# working.net
KiCad netlist of a schematic drawn in EAGLE
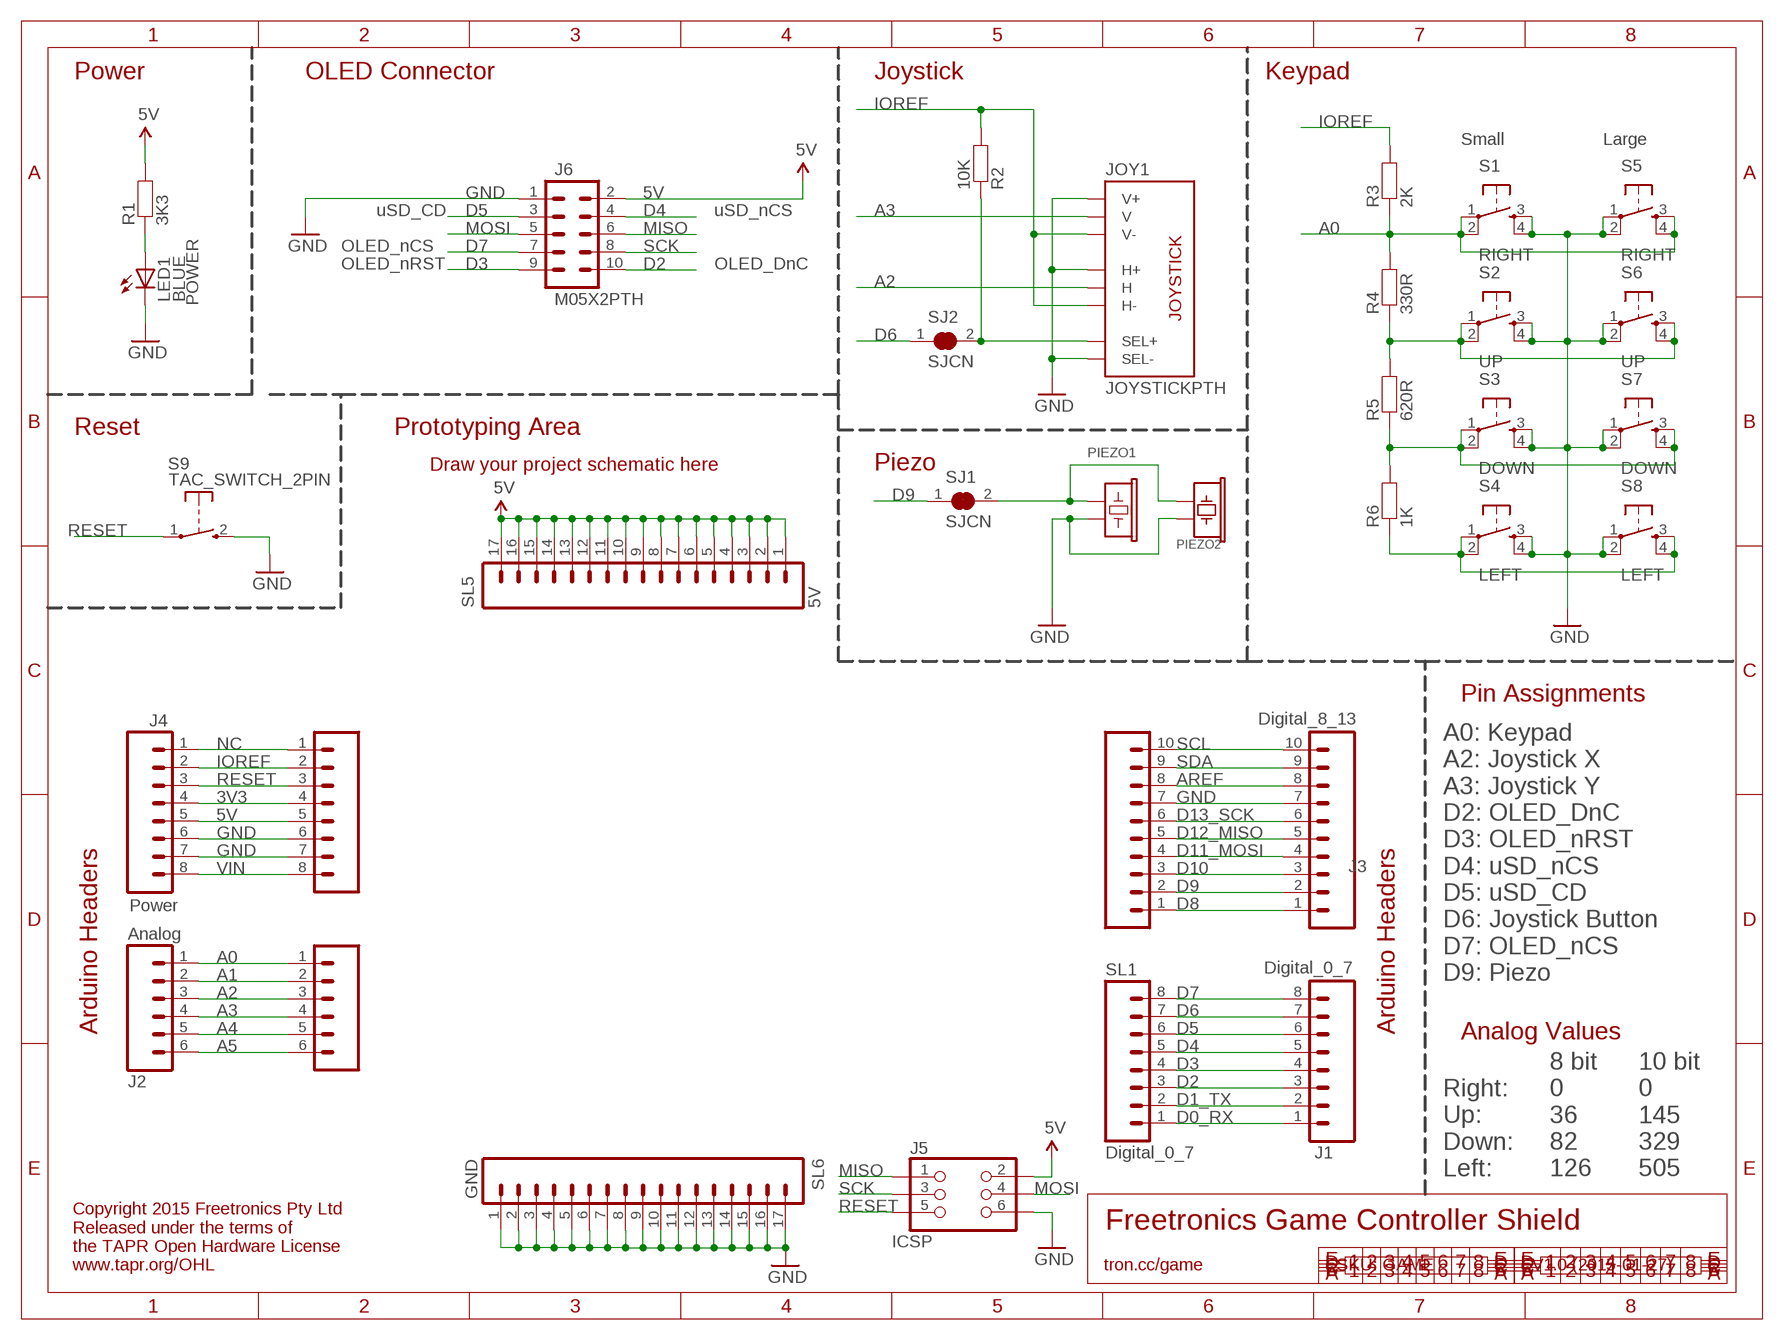
[diagram p0: schematic, sheet 1]

(export (version "E")
  (design (tool "Eeschema 10.0.6"))
  (components
    (comp (ref "J1")
      (value "Digital_0_7")
      (footprint "eagle-import:1X08")
      (libsource (lib "eagle-import") (part "M08"))
    )
    (comp (ref "J2")
      (value "Analog")
      (footprint "eagle-import:1X06")
      (libsource (lib "eagle-import") (part "M06SIP"))
    )
    (comp (ref "J3")
      (value "Digital_8_13")
      (footprint "eagle-import:1X10")
      (libsource (lib "eagle-import") (part "M100.1"))
    )
    (comp (ref "J4")
      (value "Power")
      (footprint "eagle-import:1X08")
      (libsource (lib "eagle-import") (part "M08"))
    )
    (comp (ref "J5")
      (value "ICSP")
      (footprint "eagle-import:2X03PTH")
      (libsource (lib "eagle-import") (part "ICSPPTH"))
    )
    (comp (ref "J6")
      (value "M05X2PTH")
      (footprint "eagle-import:AVR_ICSP")
      (libsource (lib "eagle-import") (part "M05X2PTH"))
    )
    (comp (ref "JOY1")
      (value "JOYSTICKPTH")
      (footprint "eagle-import:JOYSTICK")
      (libsource (lib "eagle-import") (part "JOYSTICKPTH"))
    )
    (comp (ref "LED1")
      (value "BLUE")
      (footprint "eagle-import:LED-0603")
      (libsource (lib "eagle-import") (part "LED0603"))
    )
    (comp (ref "PIEZO1")
      (value "BUZZERSMD12X12")
      (footprint "eagle-import:BUZZER-12X12-SMT")
      (libsource (lib "eagle-import") (part "BUZZERSMD12X12"))
    )
    (comp (ref "PIEZO2")
      (value "PIEZO12MM")
      (footprint "eagle-import:PIEZO12MM")
      (libsource (lib "eagle-import") (part "PIEZO12MM"))
    )
    (comp (ref "R1")
      (value "3K3")
      (footprint "eagle-import:0603")
      (libsource (lib "eagle-import") (part "RESISTOR0603"))
    )
    (comp (ref "R2")
      (value "10K")
      (footprint "eagle-import:0603")
      (libsource (lib "eagle-import") (part "RESISTOR0603"))
    )
    (comp (ref "R3")
      (value "2K")
      (footprint "eagle-import:0603")
      (libsource (lib "eagle-import") (part "RESISTOR0603"))
    )
    (comp (ref "R4")
      (value "330R")
      (footprint "eagle-import:0603")
      (libsource (lib "eagle-import") (part "RESISTOR0603"))
    )
    (comp (ref "R5")
      (value "620R")
      (footprint "eagle-import:0603")
      (libsource (lib "eagle-import") (part "RESISTOR0603"))
    )
    (comp (ref "R6")
      (value "1K")
      (footprint "eagle-import:0603")
      (libsource (lib "eagle-import") (part "RESISTOR0603"))
    )
    (comp (ref "S1")
      (value "RIGHT")
      (footprint "eagle-import:TACTILE-PTH")
      (libsource (lib "eagle-import") (part "TAC_SWITCHPTH"))
    )
    (comp (ref "S2")
      (value "UP")
      (footprint "eagle-import:TACTILE-PTH")
      (libsource (lib "eagle-import") (part "TAC_SWITCHPTH"))
    )
    (comp (ref "S3")
      (value "DOWN")
      (footprint "eagle-import:TACTILE-PTH")
      (libsource (lib "eagle-import") (part "TAC_SWITCHPTH"))
    )
    (comp (ref "S4")
      (value "LEFT")
      (footprint "eagle-import:TACTILE-PTH")
      (libsource (lib "eagle-import") (part "TAC_SWITCHPTH"))
    )
    (comp (ref "S5")
      (value "RIGHT")
      (footprint "eagle-import:TACTILE-PTH-12MM")
      (libsource (lib "eagle-import") (part "TAC_SWITCH12"))
    )
    (comp (ref "S6")
      (value "UP")
      (footprint "eagle-import:TACTILE-PTH-12MM")
      (libsource (lib "eagle-import") (part "TAC_SWITCH12"))
    )
    (comp (ref "S7")
      (value "DOWN")
      (footprint "eagle-import:TACTILE-PTH-12MM")
      (libsource (lib "eagle-import") (part "TAC_SWITCH12"))
    )
    (comp (ref "S8")
      (value "LEFT")
      (footprint "eagle-import:TACTILE-PTH-12MM")
      (libsource (lib "eagle-import") (part "TAC_SWITCH12"))
    )
    (comp (ref "S9")
      (value "TAC_SWITCH_2PIN")
      (footprint "eagle-import:TACTILE_SWITCH_SMD_2PIN_TINY")
      (libsource (lib "eagle-import") (part "TAC_SWITCH_2PIN"))
    )
    (comp (ref "SJ1")
      (value "SJCN")
      (footprint "eagle-import:SJC")
      (libsource (lib "eagle-import") (part "SJCN"))
    )
    (comp (ref "SJ2")
      (value "SJCN")
      (footprint "eagle-import:SJC")
      (libsource (lib "eagle-import") (part "SJCN"))
    )
    (comp (ref "SL1")
      (value "Digital_0_7")
      (footprint "eagle-import:1X08")
      (libsource (lib "eagle-import") (part "freetronics-original_M08"))
    )
    (comp (ref "SL2")
      (value "Analog")
      (footprint "eagle-import:1X06")
      (libsource (lib "eagle-import") (part "M06SIP"))
    )
    (comp (ref "SL3")
      (value "Digital_8_13")
      (footprint "eagle-import:1X10")
      (libsource (lib "eagle-import") (part "M100.1"))
    )
    (comp (ref "SL4")
      (value "Power")
      (footprint "eagle-import:1X08")
      (libsource (lib "eagle-import") (part "M08"))
    )
    (comp (ref "SL5")
      (value "5V")
      (footprint "eagle-import:1X17")
      (libsource (lib "eagle-import") (part "M17"))
    )
    (comp (ref "SL6")
      (value "GND")
      (footprint "eagle-import:1X17")
      (libsource (lib "eagle-import") (part "M17"))
    )
  )
  (nets
    (net (code "1") (name "/3V3") (class "Default")
      (node (ref "J4") (pin "4") (pinfunction "4_4") (pintype "passive"))
      (node (ref "SL4") (pin "4") (pinfunction "4_4") (pintype "passive"))
    )
    (net (code "2") (name "/A0") (class "Default")
      (node (ref "J2") (pin "1") (pinfunction "1_1") (pintype "passive"))
      (node (ref "R3") (pin "1") (pinfunction "1_1") (pintype "passive"))
      (node (ref "R4") (pin "2") (pinfunction "2_2") (pintype "passive"))
      (node (ref "S1") (pin "1") (pinfunction "1_1") (pintype "passive"))
      (node (ref "S1") (pin "2") (pinfunction "2_2") (pintype "passive"))
      (node (ref "S5") (pin "3") (pinfunction "3_3") (pintype "passive"))
      (node (ref "S5") (pin "4") (pinfunction "4_4") (pintype "passive"))
      (node (ref "SL2") (pin "1") (pinfunction "1_1") (pintype "passive"))
    )
    (net (code "3") (name "/A1") (class "Default")
      (node (ref "J2") (pin "2") (pinfunction "2_2") (pintype "passive"))
      (node (ref "SL2") (pin "2") (pinfunction "2_2") (pintype "passive"))
    )
    (net (code "4") (name "/A2") (class "Default")
      (node (ref "J2") (pin "3") (pinfunction "3_3") (pintype "passive"))
      (node (ref "JOY1") (pin "H2") (pinfunction "H_H2") (pintype "bidirectional"))
      (node (ref "SL2") (pin "3") (pinfunction "3_3") (pintype "passive"))
    )
    (net (code "5") (name "/A3") (class "Default")
      (node (ref "J2") (pin "4") (pinfunction "4_4") (pintype "passive"))
      (node (ref "JOY1") (pin "V2") (pinfunction "V_V2") (pintype "bidirectional"))
      (node (ref "SL2") (pin "4") (pinfunction "4_4") (pintype "passive"))
    )
    (net (code "6") (name "/A4") (class "Default")
      (node (ref "J2") (pin "5") (pinfunction "5_5") (pintype "passive"))
      (node (ref "SL2") (pin "5") (pinfunction "5_5") (pintype "passive"))
    )
    (net (code "7") (name "/A5") (class "Default")
      (node (ref "J2") (pin "6") (pinfunction "6_6") (pintype "passive"))
      (node (ref "SL2") (pin "6") (pinfunction "6_6") (pintype "passive"))
    )
    (net (code "8") (name "/AREF") (class "Default")
      (node (ref "J3") (pin "8") (pinfunction "8_8") (pintype "passive"))
      (node (ref "SL3") (pin "8") (pinfunction "8_8") (pintype "passive"))
    )
    (net (code "9") (name "/D0_RX") (class "Default")
      (node (ref "J1") (pin "1") (pinfunction "1_1") (pintype "passive"))
      (node (ref "SL1") (pin "1") (pinfunction "1_1") (pintype "passive"))
    )
    (net (code "10") (name "/D1_TX") (class "Default")
      (node (ref "J1") (pin "2") (pinfunction "2_2") (pintype "passive"))
      (node (ref "SL1") (pin "2") (pinfunction "2_2") (pintype "passive"))
    )
    (net (code "11") (name "/D2") (class "Default")
      (node (ref "J1") (pin "3") (pinfunction "3_3") (pintype "passive"))
      (node (ref "J6") (pin "10") (pinfunction "10_10") (pintype "passive"))
      (node (ref "SL1") (pin "3") (pinfunction "3_3") (pintype "passive"))
    )
    (net (code "12") (name "/D3") (class "Default")
      (node (ref "J1") (pin "4") (pinfunction "4_4") (pintype "passive"))
      (node (ref "J6") (pin "9") (pinfunction "9_9") (pintype "passive"))
      (node (ref "SL1") (pin "4") (pinfunction "4_4") (pintype "passive"))
    )
    (net (code "13") (name "/D4") (class "Default")
      (node (ref "J1") (pin "5") (pinfunction "5_5") (pintype "passive"))
      (node (ref "J6") (pin "4") (pinfunction "4_4") (pintype "passive"))
      (node (ref "SL1") (pin "5") (pinfunction "5_5") (pintype "passive"))
    )
    (net (code "14") (name "/D5") (class "Default")
      (node (ref "J1") (pin "6") (pinfunction "6_6") (pintype "passive"))
      (node (ref "J6") (pin "3") (pinfunction "3_3") (pintype "passive"))
      (node (ref "SL1") (pin "6") (pinfunction "6_6") (pintype "passive"))
    )
    (net (code "15") (name "/D6") (class "Default")
      (node (ref "J1") (pin "7") (pinfunction "7_7") (pintype "passive"))
      (node (ref "SJ2") (pin "1") (pinfunction "1_1") (pintype "passive"))
      (node (ref "SL1") (pin "7") (pinfunction "7_7") (pintype "passive"))
    )
    (net (code "16") (name "/D7") (class "Default")
      (node (ref "J1") (pin "8") (pinfunction "8_8") (pintype "passive"))
      (node (ref "J6") (pin "7") (pinfunction "7_7") (pintype "passive"))
      (node (ref "SL1") (pin "8") (pinfunction "8_8") (pintype "passive"))
    )
    (net (code "17") (name "/D8") (class "Default")
      (node (ref "J3") (pin "1") (pinfunction "1_1") (pintype "passive"))
      (node (ref "SL3") (pin "1") (pinfunction "1_1") (pintype "passive"))
    )
    (net (code "18") (name "/D9") (class "Default")
      (node (ref "J3") (pin "2") (pinfunction "2_2") (pintype "passive"))
      (node (ref "SJ1") (pin "1") (pinfunction "1_1") (pintype "passive"))
      (node (ref "SL3") (pin "2") (pinfunction "2_2") (pintype "passive"))
    )
    (net (code "19") (name "/D10") (class "Default")
      (node (ref "J3") (pin "3") (pinfunction "3_3") (pintype "passive"))
      (node (ref "SL3") (pin "3") (pinfunction "3_3") (pintype "passive"))
    )
    (net (code "20") (name "/D11_MOSI") (class "Default")
      (node (ref "J3") (pin "4") (pinfunction "4_4") (pintype "passive"))
      (node (ref "SL3") (pin "4") (pinfunction "4_4") (pintype "passive"))
    )
    (net (code "21") (name "/D12_MISO") (class "Default")
      (node (ref "J3") (pin "5") (pinfunction "5_5") (pintype "passive"))
      (node (ref "SL3") (pin "5") (pinfunction "5_5") (pintype "passive"))
    )
    (net (code "22") (name "/D13_SCK") (class "Default")
      (node (ref "J3") (pin "6") (pinfunction "6_6") (pintype "passive"))
      (node (ref "SL3") (pin "6") (pinfunction "6_6") (pintype "passive"))
    )
    (net (code "23") (name "/IOREF") (class "Default")
      (node (ref "J4") (pin "2") (pinfunction "2_2") (pintype "passive"))
      (node (ref "JOY1") (pin "H3") (pinfunction "H-_H3") (pintype "bidirectional"))
      (node (ref "JOY1") (pin "V3") (pinfunction "V-_V3") (pintype "bidirectional"))
      (node (ref "R2") (pin "2") (pinfunction "2_2") (pintype "passive"))
      (node (ref "R3") (pin "2") (pinfunction "2_2") (pintype "passive"))
      (node (ref "SL4") (pin "2") (pinfunction "2_2") (pintype "passive"))
    )
    (net (code "24") (name "/MISO") (class "Default")
      (node (ref "J5") (pin "1") (pinfunction "1_1") (pintype "passive"))
      (node (ref "J6") (pin "6") (pinfunction "6_6") (pintype "passive"))
    )
    (net (code "25") (name "/MOSI") (class "Default")
      (node (ref "J5") (pin "4") (pinfunction "4_4") (pintype "passive"))
      (node (ref "J6") (pin "5") (pinfunction "5_5") (pintype "passive"))
    )
    (net (code "26") (name "/NC") (class "Default")
      (node (ref "J4") (pin "1") (pinfunction "1_1") (pintype "passive"))
      (node (ref "SL4") (pin "1") (pinfunction "1_1") (pintype "passive"))
    )
    (net (code "27") (name "/RESET") (class "Default")
      (node (ref "J4") (pin "3") (pinfunction "3_3") (pintype "passive"))
      (node (ref "J5") (pin "5") (pinfunction "5_5") (pintype "passive"))
      (node (ref "S9") (pin "1") (pinfunction "P_1") (pintype "passive"))
      (node (ref "SL4") (pin "3") (pinfunction "3_3") (pintype "passive"))
    )
    (net (code "28") (name "/SCK") (class "Default")
      (node (ref "J5") (pin "3") (pinfunction "3_3") (pintype "passive"))
      (node (ref "J6") (pin "8") (pinfunction "8_8") (pintype "passive"))
    )
    (net (code "29") (name "/SCL") (class "Default")
      (node (ref "J3") (pin "10") (pinfunction "10_10") (pintype "passive"))
      (node (ref "SL3") (pin "10") (pinfunction "10_10") (pintype "passive"))
    )
    (net (code "30") (name "/SDA") (class "Default")
      (node (ref "J3") (pin "9") (pinfunction "9_9") (pintype "passive"))
      (node (ref "SL3") (pin "9") (pinfunction "9_9") (pintype "passive"))
    )
    (net (code "31") (name "/VIN") (class "Default")
      (node (ref "J4") (pin "8") (pinfunction "8_8") (pintype "passive"))
      (node (ref "SL4") (pin "8") (pinfunction "8_8") (pintype "passive"))
    )
    (net (code "32") (name "5V") (class "Default")
      (node (ref "J4") (pin "5") (pinfunction "5_5") (pintype "passive"))
      (node (ref "J5") (pin "2") (pinfunction "2_2") (pintype "passive"))
      (node (ref "J6") (pin "2") (pinfunction "2_2") (pintype "passive"))
      (node (ref "R1") (pin "2") (pinfunction "2_2") (pintype "passive"))
      (node (ref "SL4") (pin "5") (pinfunction "5_5") (pintype "passive"))
      (node (ref "SL5") (pin "1") (pinfunction "1_1") (pintype "passive"))
      (node (ref "SL5") (pin "10") (pinfunction "10_10") (pintype "passive"))
      (node (ref "SL5") (pin "11") (pinfunction "11_11") (pintype "passive"))
      (node (ref "SL5") (pin "12") (pinfunction "12_12") (pintype "passive"))
      (node (ref "SL5") (pin "13") (pinfunction "13_13") (pintype "passive"))
      (node (ref "SL5") (pin "14") (pinfunction "14_14") (pintype "passive"))
      (node (ref "SL5") (pin "15") (pinfunction "15_15") (pintype "passive"))
      (node (ref "SL5") (pin "16") (pinfunction "16_16") (pintype "passive"))
      (node (ref "SL5") (pin "17") (pinfunction "17_17") (pintype "passive"))
      (node (ref "SL5") (pin "2") (pinfunction "2_2") (pintype "passive"))
      (node (ref "SL5") (pin "3") (pinfunction "3_3") (pintype "passive"))
      (node (ref "SL5") (pin "4") (pinfunction "4_4") (pintype "passive"))
      (node (ref "SL5") (pin "5") (pinfunction "5_5") (pintype "passive"))
      (node (ref "SL5") (pin "6") (pinfunction "6_6") (pintype "passive"))
      (node (ref "SL5") (pin "7") (pinfunction "7_7") (pintype "passive"))
      (node (ref "SL5") (pin "8") (pinfunction "8_8") (pintype "passive"))
      (node (ref "SL5") (pin "9") (pinfunction "9_9") (pintype "passive"))
    )
    (net (code "33") (name "GND") (class "Default")
      (node (ref "J3") (pin "7") (pinfunction "7_7") (pintype "passive"))
      (node (ref "J4") (pin "6") (pinfunction "6_6") (pintype "passive"))
      (node (ref "J4") (pin "7") (pinfunction "7_7") (pintype "passive"))
      (node (ref "J5") (pin "6") (pinfunction "6_6") (pintype "passive"))
      (node (ref "J6") (pin "1") (pinfunction "1_1") (pintype "passive"))
      (node (ref "JOY1") (pin "B2A") (pinfunction "SEL-_B2A") (pintype "bidirectional"))
      (node (ref "JOY1") (pin "H1") (pinfunction "H+_H1") (pintype "bidirectional"))
      (node (ref "JOY1") (pin "V1") (pinfunction "V+_V1") (pintype "bidirectional"))
      (node (ref "LED1") (pin "C") (pinfunction "C_C") (pintype "passive"))
      (node (ref "PIEZO1") (pin "1") (pinfunction "1_1") (pintype "passive"))
      (node (ref "PIEZO2") (pin "2") (pinfunction "2_2") (pintype "bidirectional"))
      (node (ref "S1") (pin "3") (pinfunction "3_3") (pintype "passive"))
      (node (ref "S1") (pin "4") (pinfunction "4_4") (pintype "passive"))
      (node (ref "S2") (pin "3") (pinfunction "3_3") (pintype "passive"))
      (node (ref "S2") (pin "4") (pinfunction "4_4") (pintype "passive"))
      (node (ref "S3") (pin "3") (pinfunction "3_3") (pintype "passive"))
      (node (ref "S3") (pin "4") (pinfunction "4_4") (pintype "passive"))
      (node (ref "S4") (pin "3") (pinfunction "3_3") (pintype "passive"))
      (node (ref "S4") (pin "4") (pinfunction "4_4") (pintype "passive"))
      (node (ref "S5") (pin "1") (pinfunction "1_1") (pintype "passive"))
      (node (ref "S5") (pin "2") (pinfunction "2_2") (pintype "passive"))
      (node (ref "S6") (pin "1") (pinfunction "1_1") (pintype "passive"))
      (node (ref "S6") (pin "2") (pinfunction "2_2") (pintype "passive"))
      (node (ref "S7") (pin "1") (pinfunction "1_1") (pintype "passive"))
      (node (ref "S7") (pin "2") (pinfunction "2_2") (pintype "passive"))
      (node (ref "S8") (pin "1") (pinfunction "1_1") (pintype "passive"))
      (node (ref "S8") (pin "2") (pinfunction "2_2") (pintype "passive"))
      (node (ref "S9") (pin "2") (pinfunction "S_2") (pintype "passive"))
      (node (ref "SL3") (pin "7") (pinfunction "7_7") (pintype "passive"))
      (node (ref "SL4") (pin "6") (pinfunction "6_6") (pintype "passive"))
      (node (ref "SL4") (pin "7") (pinfunction "7_7") (pintype "passive"))
      (node (ref "SL6") (pin "1") (pinfunction "1_1") (pintype "passive"))
      (node (ref "SL6") (pin "10") (pinfunction "10_10") (pintype "passive"))
      (node (ref "SL6") (pin "11") (pinfunction "11_11") (pintype "passive"))
      (node (ref "SL6") (pin "12") (pinfunction "12_12") (pintype "passive"))
      (node (ref "SL6") (pin "13") (pinfunction "13_13") (pintype "passive"))
      (node (ref "SL6") (pin "14") (pinfunction "14_14") (pintype "passive"))
      (node (ref "SL6") (pin "15") (pinfunction "15_15") (pintype "passive"))
      (node (ref "SL6") (pin "16") (pinfunction "16_16") (pintype "passive"))
      (node (ref "SL6") (pin "17") (pinfunction "17_17") (pintype "passive"))
      (node (ref "SL6") (pin "2") (pinfunction "2_2") (pintype "passive"))
      (node (ref "SL6") (pin "3") (pinfunction "3_3") (pintype "passive"))
      (node (ref "SL6") (pin "4") (pinfunction "4_4") (pintype "passive"))
      (node (ref "SL6") (pin "5") (pinfunction "5_5") (pintype "passive"))
      (node (ref "SL6") (pin "6") (pinfunction "6_6") (pintype "passive"))
      (node (ref "SL6") (pin "7") (pinfunction "7_7") (pintype "passive"))
      (node (ref "SL6") (pin "8") (pinfunction "8_8") (pintype "passive"))
      (node (ref "SL6") (pin "9") (pinfunction "9_9") (pintype "passive"))
    )
    (net (code "34") (name "Net-(JOY1-SEL+)") (class "Default")
      (node (ref "JOY1") (pin "B1A") (pinfunction "SEL+_B1A") (pintype "bidirectional"))
      (node (ref "R2") (pin "1") (pinfunction "1_1") (pintype "passive"))
      (node (ref "SJ2") (pin "2") (pinfunction "2_2") (pintype "passive"))
    )
    (net (code "35") (name "Net-(LED1-PadA)") (class "Default")
      (node (ref "LED1") (pin "A") (pinfunction "A_A") (pintype "passive"))
      (node (ref "R1") (pin "1") (pinfunction "1_1") (pintype "passive"))
    )
    (net (code "36") (name "Net-(PIEZO1-Pad2)") (class "Default")
      (node (ref "PIEZO1") (pin "2") (pinfunction "2_2") (pintype "passive"))
      (node (ref "PIEZO2") (pin "1") (pinfunction "1_1") (pintype "bidirectional"))
      (node (ref "SJ1") (pin "2") (pinfunction "2_2") (pintype "passive"))
    )
    (net (code "37") (name "Net-(R4-Pad1)") (class "Default")
      (node (ref "R4") (pin "1") (pinfunction "1_1") (pintype "passive"))
      (node (ref "R5") (pin "2") (pinfunction "2_2") (pintype "passive"))
      (node (ref "S2") (pin "1") (pinfunction "1_1") (pintype "passive"))
      (node (ref "S2") (pin "2") (pinfunction "2_2") (pintype "passive"))
      (node (ref "S6") (pin "3") (pinfunction "3_3") (pintype "passive"))
      (node (ref "S6") (pin "4") (pinfunction "4_4") (pintype "passive"))
    )
    (net (code "38") (name "Net-(R5-Pad1)") (class "Default")
      (node (ref "R5") (pin "1") (pinfunction "1_1") (pintype "passive"))
      (node (ref "R6") (pin "2") (pinfunction "2_2") (pintype "passive"))
      (node (ref "S3") (pin "1") (pinfunction "1_1") (pintype "passive"))
      (node (ref "S3") (pin "2") (pinfunction "2_2") (pintype "passive"))
      (node (ref "S7") (pin "3") (pinfunction "3_3") (pintype "passive"))
      (node (ref "S7") (pin "4") (pinfunction "4_4") (pintype "passive"))
    )
    (net (code "39") (name "Net-(R6-Pad1)") (class "Default")
      (node (ref "R6") (pin "1") (pinfunction "1_1") (pintype "passive"))
      (node (ref "S4") (pin "1") (pinfunction "1_1") (pintype "passive"))
      (node (ref "S4") (pin "2") (pinfunction "2_2") (pintype "passive"))
      (node (ref "S8") (pin "3") (pinfunction "3_3") (pintype "passive"))
      (node (ref "S8") (pin "4") (pinfunction "4_4") (pintype "passive"))
    )
  )
)
